# sheet2.net
KiCad netlist of a schematic drawn in Altium Designer
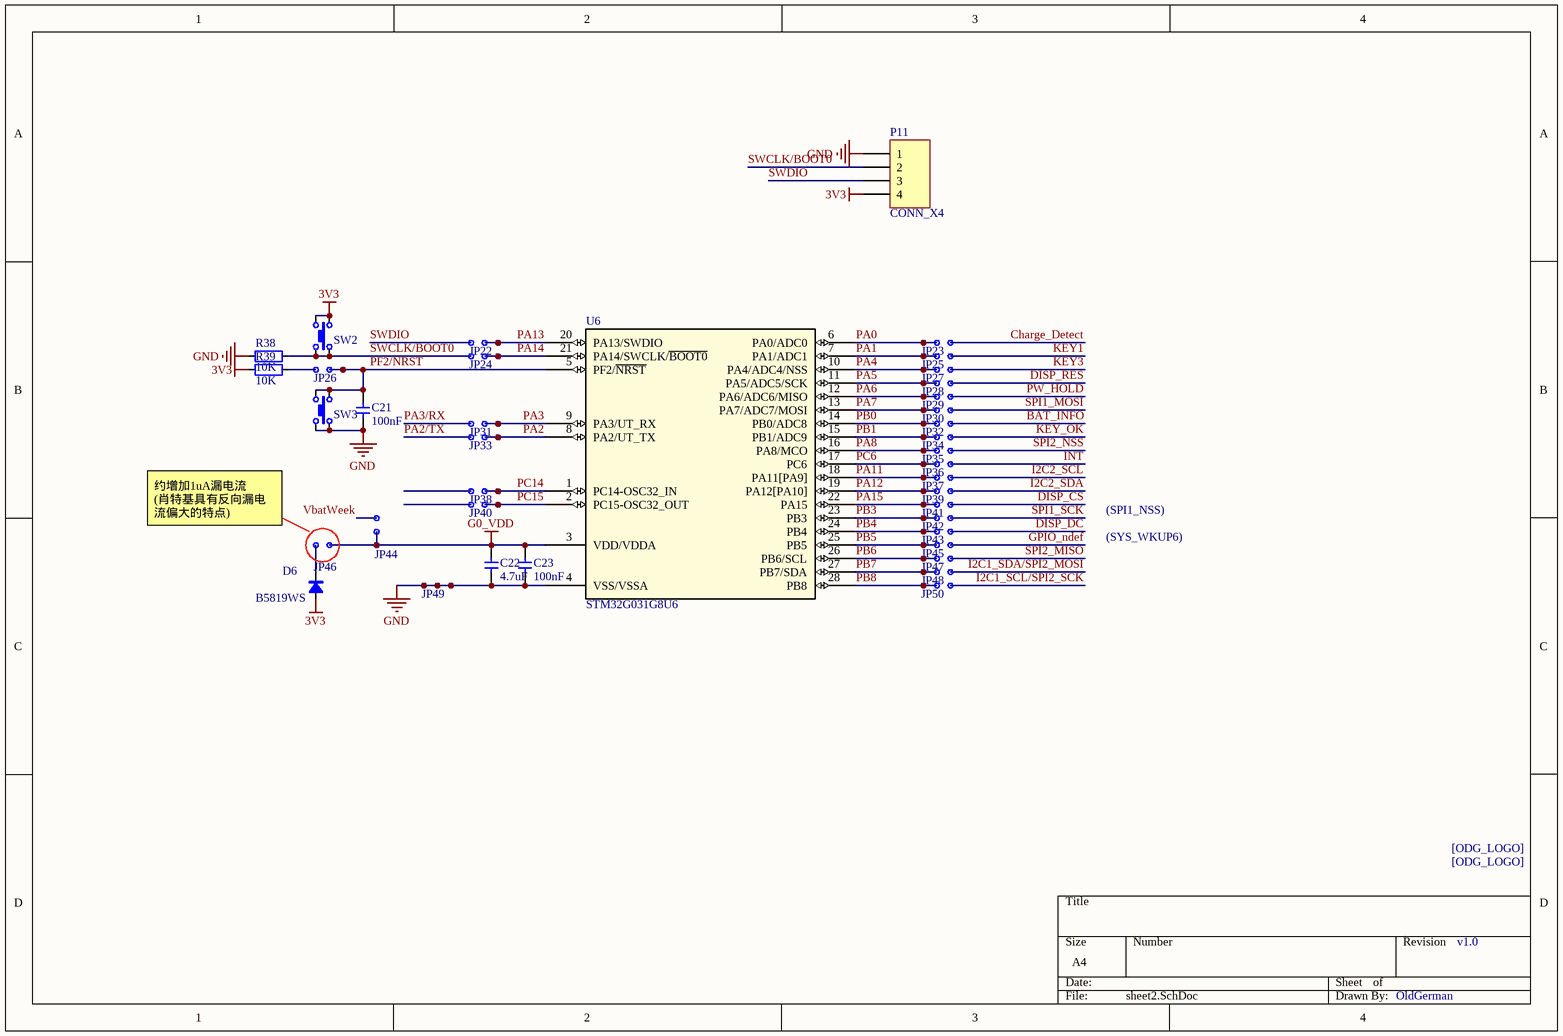
[diagram p0: sheet2.SchDoc]

(export (version "E")
  (design (tool "Eeschema 10.0.6"))
  (components
    (comp (ref "C21")
      (value "100nF")
      (footprint "C0603")
      (description "Capacitor")
      (libsource (lib "ODG_AD_Lib") (part "CAP"))
    )
    (comp (ref "C22")
      (value "4.7uF")
      (footprint "C0603")
      (description "Capacitor")
      (libsource (lib "ODG_AD_Lib") (part "CAP"))
    )
    (comp (ref "C23")
      (value "100nF")
      (footprint "C0603")
      (description "Capacitor")
      (libsource (lib "ODG_AD_Lib") (part "CAP"))
    )
    (comp (ref "D6")
      (value "B5819WS")
      (footprint "SOD-323")
      (description "肖特基二极管")
      (libsource (lib "ODG_AD_Lib") (part "DIODE"))
    )
    (comp (ref "JP22")
      (value "CONN_X3_DOT")
      (footprint "2.54mm_Male_x3")
      (libsource (lib "ODG_AD_Lib") (part "CONN_X3_DOT"))
    )
    (comp (ref "JP23")
      (value "CONN_X3_DOT")
      (footprint "2.54mm_Male_x3")
      (libsource (lib "ODG_AD_Lib") (part "CONN_X3_DOT"))
    )
    (comp (ref "JP24")
      (value "CONN_X3_DOT")
      (footprint "2.54mm_Male_x3")
      (libsource (lib "ODG_AD_Lib") (part "CONN_X3_DOT"))
    )
    (comp (ref "JP25")
      (value "CONN_X3_DOT")
      (footprint "2.54mm_Male_x3")
      (libsource (lib "ODG_AD_Lib") (part "CONN_X3_DOT"))
    )
    (comp (ref "JP26")
      (value "CONN_X3_DOT")
      (footprint "2.54mm_Male_x3")
      (libsource (lib "ODG_AD_Lib") (part "CONN_X3_DOT"))
    )
    (comp (ref "JP27")
      (value "CONN_X3_DOT")
      (footprint "2.54mm_Male_x3")
      (libsource (lib "ODG_AD_Lib") (part "CONN_X3_DOT"))
    )
    (comp (ref "JP28")
      (value "CONN_X3_DOT")
      (footprint "2.54mm_Male_x3")
      (libsource (lib "ODG_AD_Lib") (part "CONN_X3_DOT"))
    )
    (comp (ref "JP29")
      (value "CONN_X3_DOT")
      (footprint "2.54mm_Male_x3")
      (libsource (lib "ODG_AD_Lib") (part "CONN_X3_DOT"))
    )
    (comp (ref "JP30")
      (value "CONN_X3_DOT")
      (footprint "2.54mm_Male_x3")
      (libsource (lib "ODG_AD_Lib") (part "CONN_X3_DOT"))
    )
    (comp (ref "JP31")
      (value "CONN_X3_DOT")
      (footprint "2.54mm_Male_x3")
      (libsource (lib "ODG_AD_Lib") (part "CONN_X3_DOT"))
    )
    (comp (ref "JP32")
      (value "CONN_X3_DOT")
      (footprint "2.54mm_Male_x3")
      (libsource (lib "ODG_AD_Lib") (part "CONN_X3_DOT"))
    )
    (comp (ref "JP33")
      (value "CONN_X3_DOT")
      (footprint "2.54mm_Male_x3")
      (libsource (lib "ODG_AD_Lib") (part "CONN_X3_DOT"))
    )
    (comp (ref "JP34")
      (value "CONN_X3_DOT")
      (footprint "2.54mm_Male_x3")
      (libsource (lib "ODG_AD_Lib") (part "CONN_X3_DOT"))
    )
    (comp (ref "JP35")
      (value "CONN_X3_DOT")
      (footprint "2.54mm_Male_x3")
      (libsource (lib "ODG_AD_Lib") (part "CONN_X3_DOT"))
    )
    (comp (ref "JP36")
      (value "CONN_X3_DOT")
      (footprint "2.54mm_Male_x3")
      (libsource (lib "ODG_AD_Lib") (part "CONN_X3_DOT"))
    )
    (comp (ref "JP37")
      (value "CONN_X3_DOT")
      (footprint "2.54mm_Male_x3")
      (libsource (lib "ODG_AD_Lib") (part "CONN_X3_DOT"))
    )
    (comp (ref "JP38")
      (value "CONN_X3_DOT")
      (footprint "2.54mm_Male_x3")
      (libsource (lib "ODG_AD_Lib") (part "CONN_X3_DOT"))
    )
    (comp (ref "JP39")
      (value "CONN_X3_DOT")
      (footprint "2.54mm_Male_x3")
      (libsource (lib "ODG_AD_Lib") (part "CONN_X3_DOT"))
    )
    (comp (ref "JP40")
      (value "CONN_X3_DOT")
      (footprint "2.54mm_Male_x3")
      (libsource (lib "ODG_AD_Lib") (part "CONN_X3_DOT"))
    )
    (comp (ref "JP41")
      (value "CONN_X3_DOT")
      (footprint "2.54mm_Male_x3")
      (libsource (lib "ODG_AD_Lib") (part "CONN_X3_DOT"))
    )
    (comp (ref "JP42")
      (value "CONN_X3_DOT")
      (footprint "2.54mm_Male_x3")
      (libsource (lib "ODG_AD_Lib") (part "CONN_X3_DOT"))
    )
    (comp (ref "JP43")
      (value "CONN_X3_DOT")
      (footprint "2.54mm_Male_x3")
      (libsource (lib "ODG_AD_Lib") (part "CONN_X3_DOT"))
    )
    (comp (ref "JP44")
      (value "CONN_X3_DOT")
      (footprint "2.54mm_Male_x3")
      (libsource (lib "ODG_AD_Lib") (part "CONN_X3_DOT"))
    )
    (comp (ref "JP45")
      (value "CONN_X3_DOT")
      (footprint "2.54mm_Male_x3")
      (libsource (lib "ODG_AD_Lib") (part "CONN_X3_DOT"))
    )
    (comp (ref "JP46")
      (value "CONN_X2_DOT")
      (footprint "2.54mm_Male_x2")
      (libsource (lib "ODG_AD_Lib") (part "CONN_X2_DOT"))
    )
    (comp (ref "JP47")
      (value "CONN_X3_DOT")
      (footprint "2.54mm_Male_x3")
      (libsource (lib "ODG_AD_Lib") (part "CONN_X3_DOT"))
    )
    (comp (ref "JP48")
      (value "CONN_X3_DOT")
      (footprint "2.54mm_Male_x3")
      (libsource (lib "ODG_AD_Lib") (part "CONN_X3_DOT"))
    )
    (comp (ref "JP49")
      (value "CONN_X3_DOT")
      (footprint "2.54mm_Male_x3")
      (libsource (lib "ODG_AD_Lib") (part "CONN_X3_DOT"))
    )
    (comp (ref "JP50")
      (value "CONN_X3_DOT")
      (footprint "2.54mm_Male_x3")
      (libsource (lib "ODG_AD_Lib") (part "CONN_X3_DOT"))
    )
    (comp (ref "ODG1")
      (value "ODG_LOGO")
      (footprint "ODG_LOGO_soldermask")
      (libsource (lib "ODG_AD_Lib") (part "ODG_LOGO"))
    )
    (comp (ref "ODG2")
      (value "ODG_LOGO")
      (footprint "ODG_LOGO_soldermask")
      (libsource (lib "ODG_AD_Lib") (part "ODG_LOGO"))
    )
    (comp (ref "P11")
      (value "CONN_X4")
      (footprint "2.54mm_Male_x4")
      (libsource (lib "ODG_AD_Lib") (part "CONN_X4"))
    )
    (comp (ref "R38")
      (value "10K")
      (footprint "R0603")
      (description "Resistor")
      (libsource (lib "ODG_AD_Lib") (part "RES"))
    )
    (comp (ref "R39")
      (value "10K")
      (footprint "R0603")
      (description "Resistor")
      (libsource (lib "ODG_AD_Lib") (part "RES"))
    )
    (comp (ref "SW2")
      (value "Button-4P")
      (footprint "SWITCH_3X4X2.5_4PIN_SMD")
      (description "Button")
      (libsource (lib "ODG_AD_Lib") (part "Button-4P"))
    )
    (comp (ref "SW3")
      (value "Button-4P")
      (footprint "SWITCH_3X4X2.5_4PIN_SMD")
      (description "Button")
      (libsource (lib "ODG_AD_Lib") (part "Button-4P"))
    )
    (comp (ref "U6")
      (value "STM32G031G8U6")
      (footprint "UFQFPN28-4x4mm_ODG")
      (description "No Description Available")
      (fields (field (name "COPYRIGHT") "Copyright (C) 2022 Ultra Librarian. All rights reserved."))
      (libsource (lib "ODG_AD_Lib") (part "STM32G031G8U6"))
    )
  )
  (nets
    (net (code "1") (name "/BAT_INFO") (class "Default")
      (node (ref "JP32") (pin "3") (pinfunction "3_3") (pintype "passive"))
    )
    (net (code "2") (name "/Charge_Detect") (class "Default")
      (node (ref "JP23") (pin "3") (pinfunction "3_3") (pintype "passive"))
    )
    (net (code "3") (name "/DISP_CS") (class "Default")
      (node (ref "JP41") (pin "3") (pinfunction "3_3") (pintype "passive"))
    )
    (net (code "4") (name "/DISP_DC") (class "Default")
      (node (ref "JP43") (pin "3") (pinfunction "3_3") (pintype "passive"))
    )
    (net (code "5") (name "/DISP_RES") (class "Default")
      (node (ref "JP28") (pin "3") (pinfunction "3_3") (pintype "passive"))
    )
    (net (code "6") (name "/GPIO_ndef") (class "Default")
      (node (ref "JP45") (pin "3") (pinfunction "3_3") (pintype "passive"))
    )
    (net (code "7") (name "/I2C1_SCL{slash}SPI2_SCK") (class "Default")
      (node (ref "JP50") (pin "3") (pinfunction "3_3") (pintype "passive"))
    )
    (net (code "8") (name "/I2C1_SDA{slash}SPI2_MOSI") (class "Default")
      (node (ref "JP48") (pin "3") (pinfunction "3_3") (pintype "passive"))
    )
    (net (code "9") (name "/I2C2_SCL") (class "Default")
      (node (ref "JP37") (pin "3") (pinfunction "3_3") (pintype "passive"))
    )
    (net (code "10") (name "/I2C2_SDA") (class "Default")
      (node (ref "JP39") (pin "3") (pinfunction "3_3") (pintype "passive"))
    )
    (net (code "11") (name "/INT") (class "Default")
      (node (ref "JP36") (pin "3") (pinfunction "3_3") (pintype "passive"))
    )
    (net (code "12") (name "/KEY1") (class "Default")
      (node (ref "JP25") (pin "3") (pinfunction "3_3") (pintype "passive"))
    )
    (net (code "13") (name "/KEY3") (class "Default")
      (node (ref "JP27") (pin "3") (pinfunction "3_3") (pintype "passive"))
    )
    (net (code "14") (name "/KEY_OK") (class "Default")
      (node (ref "JP34") (pin "3") (pinfunction "3_3") (pintype "passive"))
    )
    (net (code "15") (name "/PA0") (class "Default")
      (node (ref "JP23") (pin "1") (pinfunction "1_1") (pintype "passive"))
      (node (ref "JP23") (pin "2") (pinfunction "2_2") (pintype "passive"))
      (node (ref "U6") (pin "6") (pinfunction "PA0/ADC0_6") (pintype "bidirectional"))
    )
    (net (code "16") (name "/PA1") (class "Default")
      (node (ref "JP25") (pin "1") (pinfunction "1_1") (pintype "passive"))
      (node (ref "JP25") (pin "2") (pinfunction "2_2") (pintype "passive"))
      (node (ref "U6") (pin "7") (pinfunction "PA1/ADC1_7") (pintype "bidirectional"))
    )
    (net (code "17") (name "/PA2") (class "Default")
      (node (ref "JP33") (pin "2") (pinfunction "2_2") (pintype "passive"))
      (node (ref "JP33") (pin "3") (pinfunction "3_3") (pintype "passive"))
      (node (ref "U6") (pin "8") (pinfunction "PA2/UT_TX_8") (pintype "bidirectional"))
    )
    (net (code "18") (name "/PA2{slash}TX") (class "Default")
      (node (ref "JP33") (pin "1") (pinfunction "1_1") (pintype "passive"))
    )
    (net (code "19") (name "/PA3") (class "Default")
      (node (ref "JP31") (pin "2") (pinfunction "2_2") (pintype "passive"))
      (node (ref "JP31") (pin "3") (pinfunction "3_3") (pintype "passive"))
      (node (ref "U6") (pin "9") (pinfunction "PA3/UT_RX_9") (pintype "bidirectional"))
    )
    (net (code "20") (name "/PA3{slash}RX") (class "Default")
      (node (ref "JP31") (pin "1") (pinfunction "1_1") (pintype "passive"))
    )
    (net (code "21") (name "/PA4") (class "Default")
      (node (ref "JP27") (pin "1") (pinfunction "1_1") (pintype "passive"))
      (node (ref "JP27") (pin "2") (pinfunction "2_2") (pintype "passive"))
      (node (ref "U6") (pin "10") (pinfunction "PA4/ADC4/NSS_10") (pintype "bidirectional"))
    )
    (net (code "22") (name "/PA5") (class "Default")
      (node (ref "JP28") (pin "1") (pinfunction "1_1") (pintype "passive"))
      (node (ref "JP28") (pin "2") (pinfunction "2_2") (pintype "passive"))
      (node (ref "U6") (pin "11") (pinfunction "PA5/ADC5/SCK_11") (pintype "bidirectional"))
    )
    (net (code "23") (name "/PA6") (class "Default")
      (node (ref "JP29") (pin "1") (pinfunction "1_1") (pintype "passive"))
      (node (ref "JP29") (pin "2") (pinfunction "2_2") (pintype "passive"))
      (node (ref "U6") (pin "12") (pinfunction "PA6/ADC6/MISO_12") (pintype "bidirectional"))
    )
    (net (code "24") (name "/PA7") (class "Default")
      (node (ref "JP30") (pin "1") (pinfunction "1_1") (pintype "passive"))
      (node (ref "JP30") (pin "2") (pinfunction "2_2") (pintype "passive"))
      (node (ref "U6") (pin "13") (pinfunction "PA7/ADC7/MOSI_13") (pintype "bidirectional"))
    )
    (net (code "25") (name "/PA8") (class "Default")
      (node (ref "JP35") (pin "1") (pinfunction "1_1") (pintype "passive"))
      (node (ref "JP35") (pin "2") (pinfunction "2_2") (pintype "passive"))
      (node (ref "U6") (pin "16") (pinfunction "PA8/MCO_16") (pintype "bidirectional"))
    )
    (net (code "26") (name "/PA11") (class "Default")
      (node (ref "JP37") (pin "1") (pinfunction "1_1") (pintype "passive"))
      (node (ref "JP37") (pin "2") (pinfunction "2_2") (pintype "passive"))
      (node (ref "U6") (pin "18") (pinfunction "PA11[PA9]_18") (pintype "bidirectional"))
    )
    (net (code "27") (name "/PA12") (class "Default")
      (node (ref "JP39") (pin "1") (pinfunction "1_1") (pintype "passive"))
      (node (ref "JP39") (pin "2") (pinfunction "2_2") (pintype "passive"))
      (node (ref "U6") (pin "19") (pinfunction "PA12[PA10]_19") (pintype "bidirectional"))
    )
    (net (code "28") (name "/PA13") (class "Default")
      (node (ref "JP22") (pin "2") (pinfunction "2_2") (pintype "passive"))
      (node (ref "JP22") (pin "3") (pinfunction "3_3") (pintype "passive"))
      (node (ref "U6") (pin "20") (pinfunction "PA13/SWDIO_20") (pintype "bidirectional"))
    )
    (net (code "29") (name "/PA14") (class "Default")
      (node (ref "JP24") (pin "2") (pinfunction "2_2") (pintype "passive"))
      (node (ref "JP24") (pin "3") (pinfunction "3_3") (pintype "passive"))
      (node (ref "U6") (pin "21") (pinfunction "PA14/SWCLK/~{BOOT0}_21") (pintype "bidirectional"))
    )
    (net (code "30") (name "/PA15") (class "Default")
      (node (ref "JP41") (pin "1") (pinfunction "1_1") (pintype "passive"))
      (node (ref "JP41") (pin "2") (pinfunction "2_2") (pintype "passive"))
      (node (ref "U6") (pin "22") (pinfunction "PA15_22") (pintype "bidirectional"))
    )
    (net (code "31") (name "/PB0") (class "Default")
      (node (ref "JP32") (pin "1") (pinfunction "1_1") (pintype "passive"))
      (node (ref "JP32") (pin "2") (pinfunction "2_2") (pintype "passive"))
      (node (ref "U6") (pin "14") (pinfunction "PB0/ADC8_14") (pintype "bidirectional"))
    )
    (net (code "32") (name "/PB1") (class "Default")
      (node (ref "JP34") (pin "1") (pinfunction "1_1") (pintype "passive"))
      (node (ref "JP34") (pin "2") (pinfunction "2_2") (pintype "passive"))
      (node (ref "U6") (pin "15") (pinfunction "PB1/ADC9_15") (pintype "bidirectional"))
    )
    (net (code "33") (name "/PB3") (class "Default")
      (node (ref "JP42") (pin "1") (pinfunction "1_1") (pintype "passive"))
      (node (ref "JP42") (pin "2") (pinfunction "2_2") (pintype "passive"))
      (node (ref "U6") (pin "23") (pinfunction "PB3_23") (pintype "bidirectional"))
    )
    (net (code "34") (name "/PB4") (class "Default")
      (node (ref "JP43") (pin "1") (pinfunction "1_1") (pintype "passive"))
      (node (ref "JP43") (pin "2") (pinfunction "2_2") (pintype "passive"))
      (node (ref "U6") (pin "24") (pinfunction "PB4_24") (pintype "bidirectional"))
    )
    (net (code "35") (name "/PB5") (class "Default")
      (node (ref "JP45") (pin "1") (pinfunction "1_1") (pintype "passive"))
      (node (ref "JP45") (pin "2") (pinfunction "2_2") (pintype "passive"))
      (node (ref "U6") (pin "25") (pinfunction "PB5_25") (pintype "bidirectional"))
    )
    (net (code "36") (name "/PB6") (class "Default")
      (node (ref "JP47") (pin "1") (pinfunction "1_1") (pintype "passive"))
      (node (ref "JP47") (pin "2") (pinfunction "2_2") (pintype "passive"))
      (node (ref "U6") (pin "26") (pinfunction "PB6/SCL_26") (pintype "bidirectional"))
    )
    (net (code "37") (name "/PB7") (class "Default")
      (node (ref "JP48") (pin "1") (pinfunction "1_1") (pintype "passive"))
      (node (ref "JP48") (pin "2") (pinfunction "2_2") (pintype "passive"))
      (node (ref "U6") (pin "27") (pinfunction "PB7/SDA_27") (pintype "bidirectional"))
    )
    (net (code "38") (name "/PB8") (class "Default")
      (node (ref "JP50") (pin "1") (pinfunction "1_1") (pintype "passive"))
      (node (ref "JP50") (pin "2") (pinfunction "2_2") (pintype "passive"))
      (node (ref "U6") (pin "28") (pinfunction "PB8_28") (pintype "bidirectional"))
    )
    (net (code "39") (name "/PC6") (class "Default")
      (node (ref "JP36") (pin "1") (pinfunction "1_1") (pintype "passive"))
      (node (ref "JP36") (pin "2") (pinfunction "2_2") (pintype "passive"))
      (node (ref "U6") (pin "17") (pinfunction "PC6_17") (pintype "bidirectional"))
    )
    (net (code "40") (name "/PC14") (class "Default")
      (node (ref "JP38") (pin "2") (pinfunction "2_2") (pintype "passive"))
      (node (ref "JP38") (pin "3") (pinfunction "3_3") (pintype "passive"))
      (node (ref "U6") (pin "1") (pinfunction "PC14-OSC32_IN_1") (pintype "bidirectional"))
    )
    (net (code "41") (name "/PC15") (class "Default")
      (node (ref "JP40") (pin "2") (pinfunction "2_2") (pintype "passive"))
      (node (ref "JP40") (pin "3") (pinfunction "3_3") (pintype "passive"))
      (node (ref "U6") (pin "2") (pinfunction "PC15-OSC32_OUT_2") (pintype "bidirectional"))
    )
    (net (code "42") (name "/PF2{slash}~{NRST}") (class "Default")
      (node (ref "C21") (pin "1") (pinfunction "1_1") (pintype "passive"))
      (node (ref "JP26") (pin "2") (pinfunction "2_2") (pintype "passive"))
      (node (ref "JP26") (pin "3") (pinfunction "3_3") (pintype "passive"))
      (node (ref "SW3") (pin "3") (pinfunction "3_3") (pintype "passive"))
      (node (ref "SW3") (pin "4") (pinfunction "4_4") (pintype "passive"))
      (node (ref "U6") (pin "5") (pinfunction "PF2/~{NRST}_5") (pintype "bidirectional"))
    )
    (net (code "43") (name "/PW_HOLD") (class "Default")
      (node (ref "JP29") (pin "3") (pinfunction "3_3") (pintype "passive"))
    )
    (net (code "44") (name "/SPI1_MOSI") (class "Default")
      (node (ref "JP30") (pin "3") (pinfunction "3_3") (pintype "passive"))
    )
    (net (code "45") (name "/SPI1_SCK") (class "Default")
      (node (ref "JP42") (pin "3") (pinfunction "3_3") (pintype "passive"))
    )
    (net (code "46") (name "/SPI2_MISO") (class "Default")
      (node (ref "JP47") (pin "3") (pinfunction "3_3") (pintype "passive"))
    )
    (net (code "47") (name "/SPI2_NSS") (class "Default")
      (node (ref "JP35") (pin "3") (pinfunction "3_3") (pintype "passive"))
    )
    (net (code "48") (name "/SWCLK{slash}BOOT0") (class "Default")
      (node (ref "JP24") (pin "1") (pinfunction "1_1") (pintype "passive"))
      (node (ref "P11") (pin "2") (pinfunction "2_2") (pintype "passive"))
      (node (ref "R38") (pin "1") (pinfunction "1_1") (pintype "passive"))
      (node (ref "SW2") (pin "1") (pinfunction "1_1") (pintype "passive"))
      (node (ref "SW2") (pin "2") (pinfunction "2_2") (pintype "passive"))
    )
    (net (code "49") (name "/SWDIO") (class "Default")
      (node (ref "JP22") (pin "1") (pinfunction "1_1") (pintype "passive"))
      (node (ref "P11") (pin "3") (pinfunction "3_3") (pintype "passive"))
    )
    (net (code "50") (name "/VbatWeek") (class "Default")
      (node (ref "JP44") (pin "1") (pinfunction "1_1") (pintype "passive"))
    )
    (net (code "51") (name "3V3") (class "Default")
      (node (ref "D6") (pin "1") (pinfunction "A_1") (pintype "passive"))
      (node (ref "P11") (pin "4") (pinfunction "4_4") (pintype "passive"))
      (node (ref "R39") (pin "2") (pinfunction "2_2") (pintype "passive"))
      (node (ref "SW2") (pin "3") (pinfunction "3_3") (pintype "passive"))
      (node (ref "SW2") (pin "4") (pinfunction "4_4") (pintype "passive"))
    )
    (net (code "52") (name "G0_VDD") (class "Default")
      (node (ref "C22") (pin "1") (pinfunction "1_1") (pintype "passive"))
      (node (ref "C23") (pin "1") (pinfunction "1_1") (pintype "passive"))
      (node (ref "JP44") (pin "2") (pinfunction "2_2") (pintype "passive"))
      (node (ref "JP44") (pin "3") (pinfunction "3_3") (pintype "passive"))
      (node (ref "JP46") (pin "1") (pinfunction "1_1") (pintype "passive"))
      (node (ref "U6") (pin "3") (pinfunction "VDD/VDDA_3") (pintype "power_in"))
    )
    (net (code "53") (name "GND") (class "Default")
      (node (ref "C21") (pin "2") (pinfunction "2_2") (pintype "passive"))
      (node (ref "C22") (pin "2") (pinfunction "2_2") (pintype "passive"))
      (node (ref "C23") (pin "2") (pinfunction "2_2") (pintype "passive"))
      (node (ref "JP49") (pin "1") (pinfunction "1_1") (pintype "passive"))
      (node (ref "JP49") (pin "2") (pinfunction "2_2") (pintype "passive"))
      (node (ref "JP49") (pin "3") (pinfunction "3_3") (pintype "passive"))
      (node (ref "P11") (pin "1") (pinfunction "1_1") (pintype "passive"))
      (node (ref "R38") (pin "2") (pinfunction "2_2") (pintype "passive"))
      (node (ref "SW3") (pin "1") (pinfunction "1_1") (pintype "passive"))
      (node (ref "SW3") (pin "2") (pinfunction "2_2") (pintype "passive"))
      (node (ref "U6") (pin "4") (pinfunction "VSS/VSSA_4") (pintype "power_in"))
    )
    (net (code "54") (name "Net-(D6-C)") (class "Default")
      (node (ref "D6") (pin "2") (pinfunction "C_2") (pintype "passive"))
      (node (ref "JP46") (pin "2") (pinfunction "2_2") (pintype "passive"))
    )
    (net (code "55") (name "Net-(JP26-Pad1)") (class "Default")
      (node (ref "JP26") (pin "1") (pinfunction "1_1") (pintype "passive"))
      (node (ref "R39") (pin "1") (pinfunction "1_1") (pintype "passive"))
    )
    (net (code "56") (name "unconnected-(JP38-Pad1)") (class "Default")
      (node (ref "JP38") (pin "1") (pinfunction "1_1") (pintype "passive"))
    )
    (net (code "57") (name "unconnected-(JP40-Pad1)") (class "Default")
      (node (ref "JP40") (pin "1") (pinfunction "1_1") (pintype "passive"))
    )
  )
)
